# RX.net
KiCad netlist of a schematic drawn in EAGLE
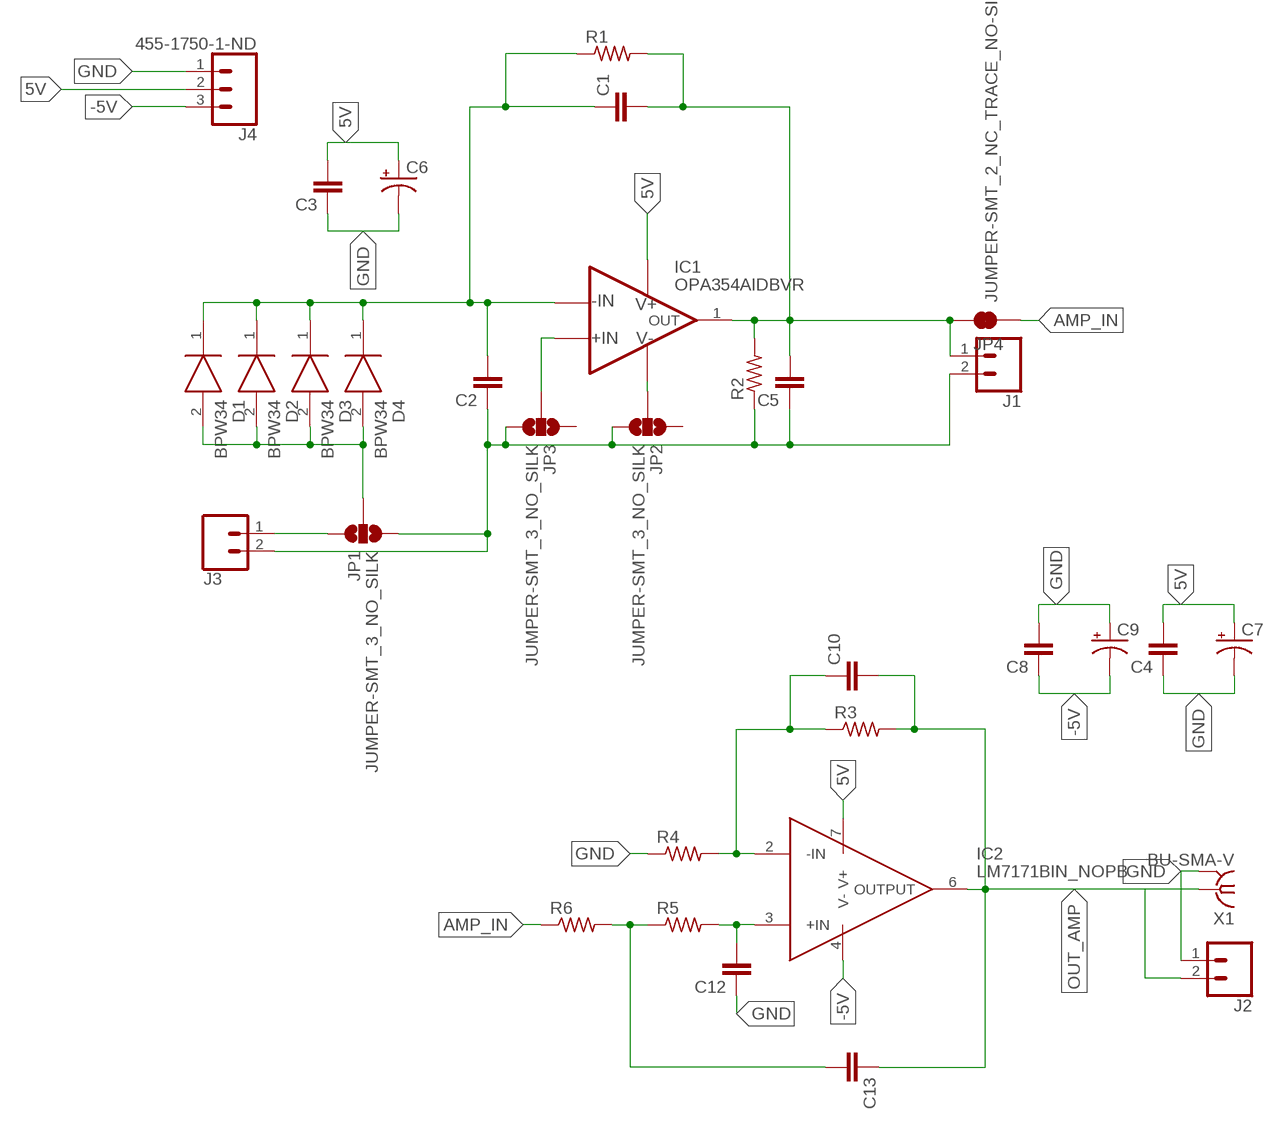
[diagram p0: schematic, sheet 1]
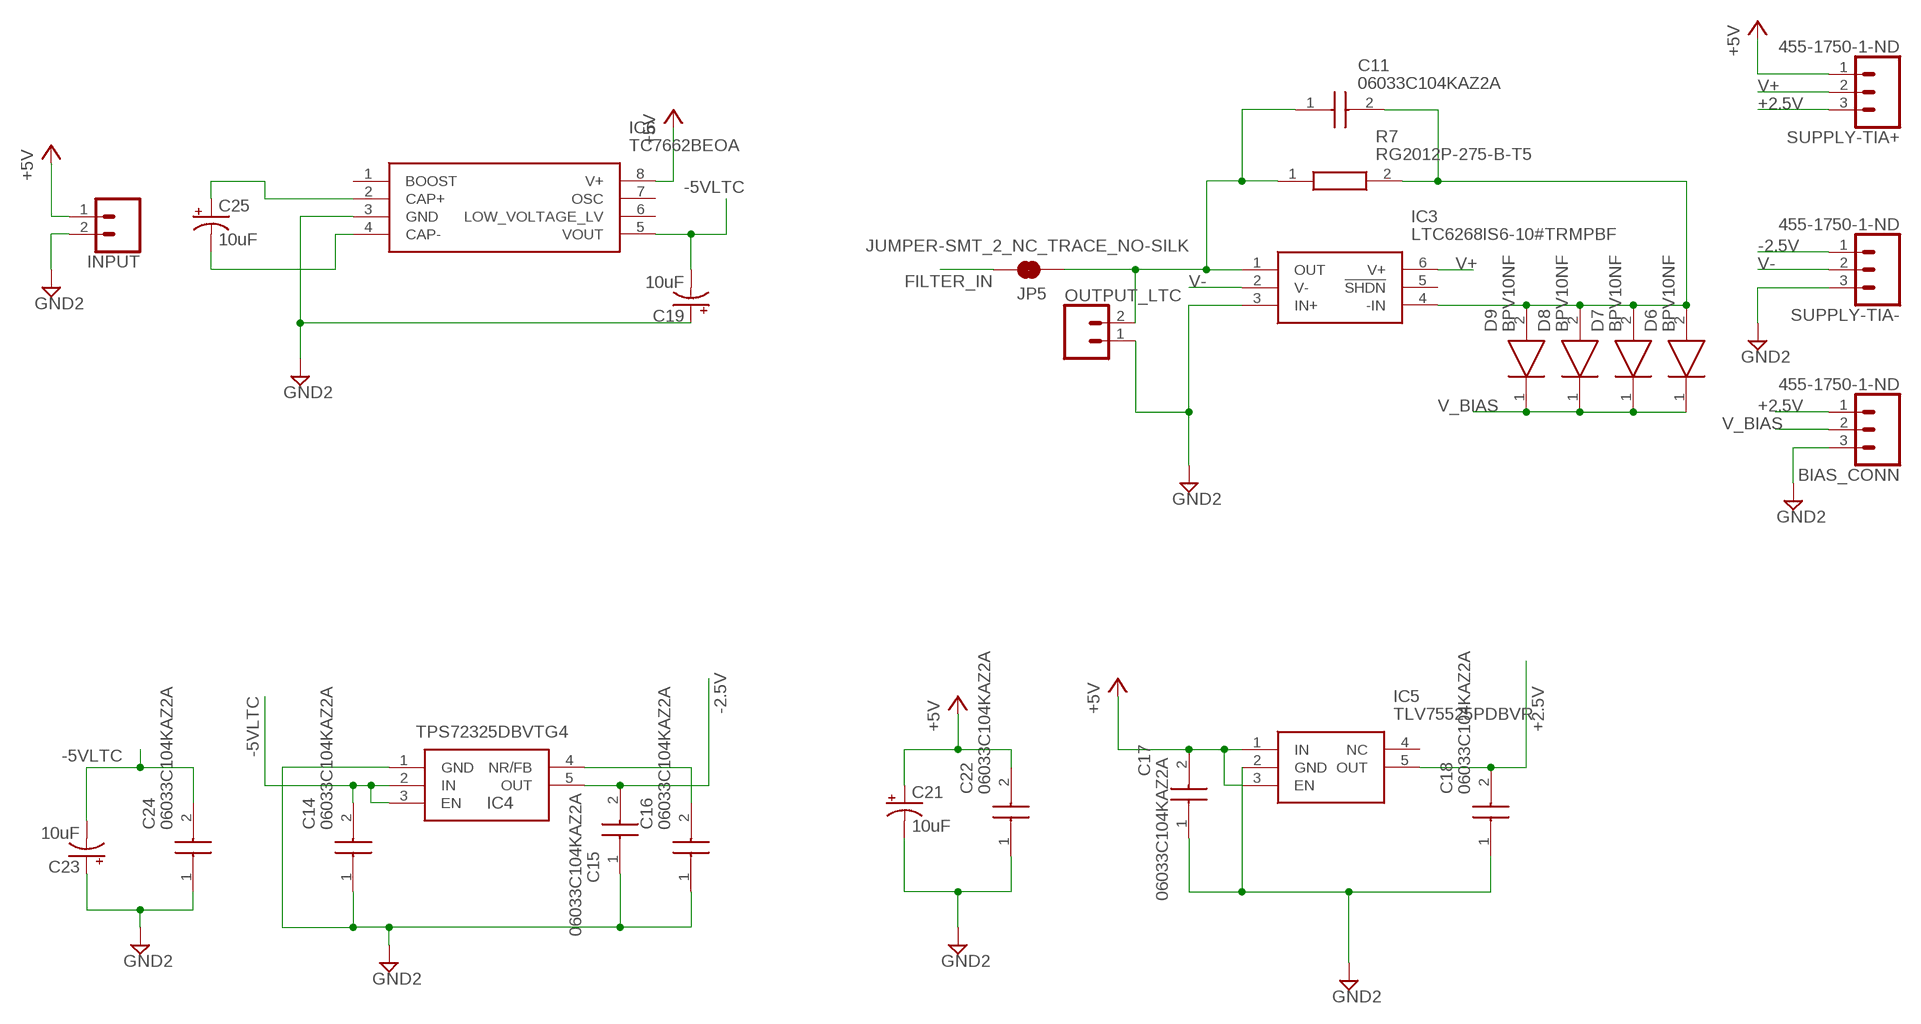
[diagram p1: schematic, sheet 2]
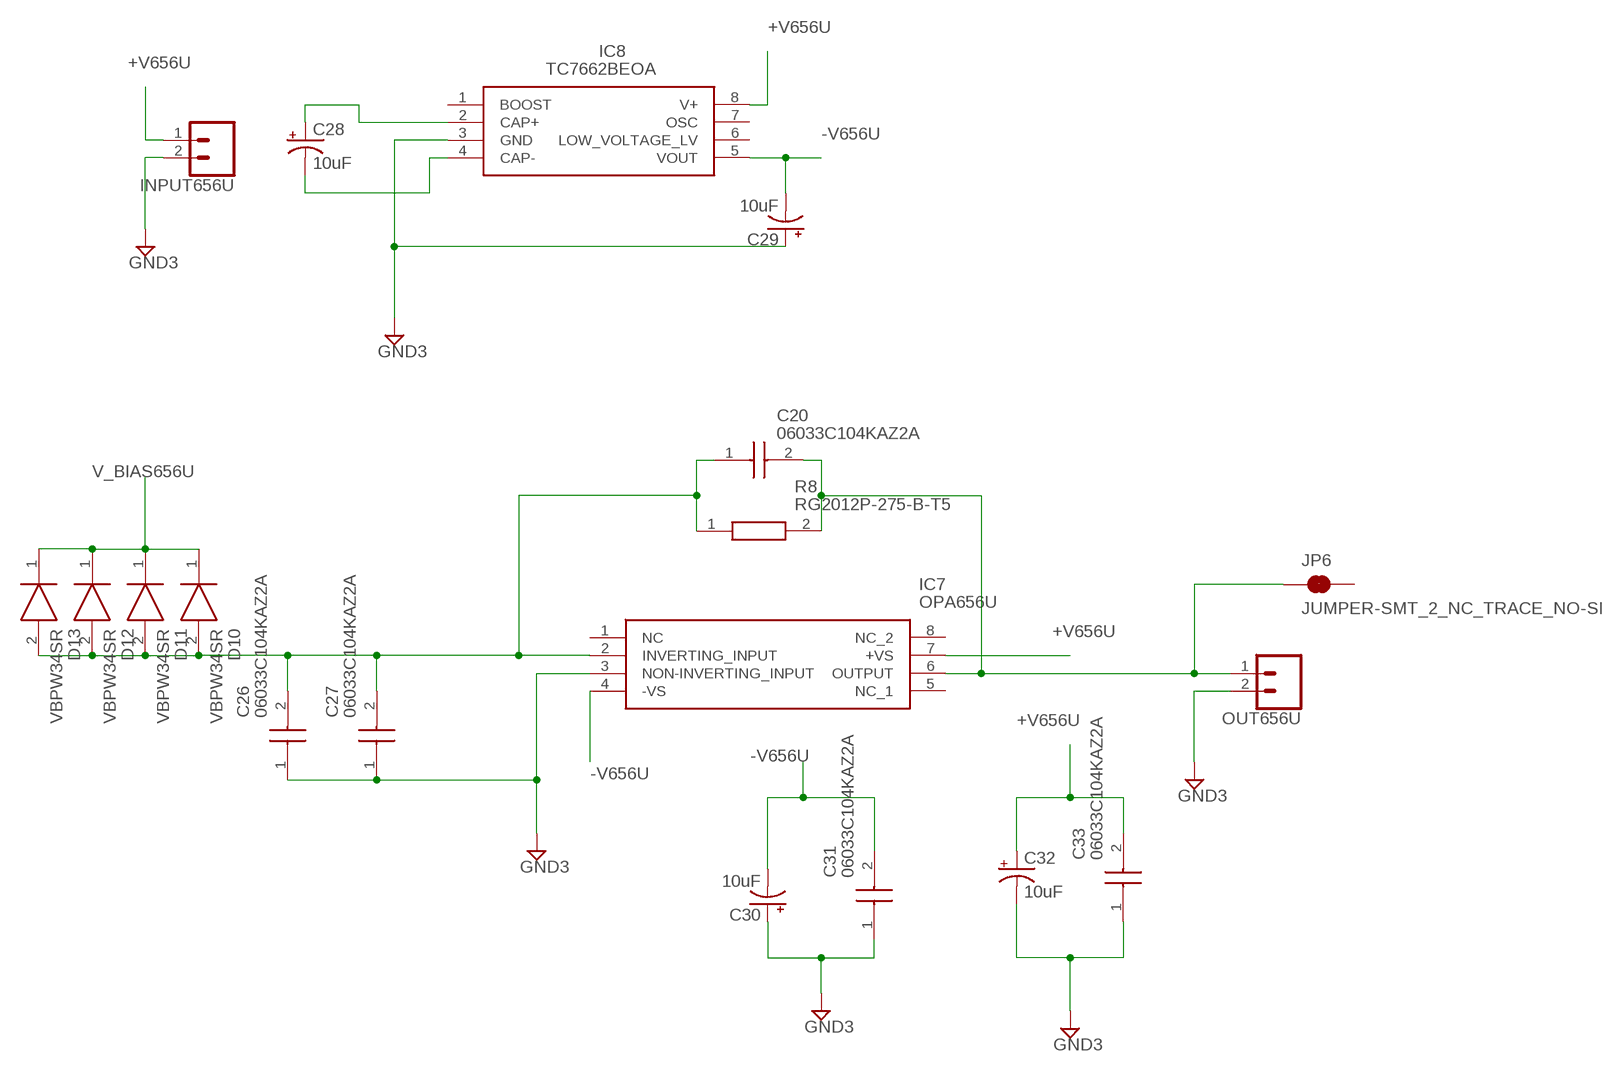
[diagram p2: schematic, sheet 3]

(export (version "E")
  (design (tool "Eeschema 10.0.6"))
  (components
    (comp (ref "BIAS_CONN")
      (value "455-1750-1-ND")
      (footprint "eagle-import:1X03")
      (libsource (lib "eagle-import") (part "CONN_03"))
    )
    (comp (ref "C11")
      (value "06033C104KAZ2A")
      (footprint "eagle-import:CAPC1608X90N")
      (fields
        (field (name "MOUSER_PART_NUMBER") "581-06033C104KAZ2A")
        (field (name "RS_PART_NUMBER") "1356596")
      )
      (libsource (lib "eagle-import") (part "06033C104KAZ2A"))
    )
    (comp (ref "C14")
      (value "06033C104KAZ2A")
      (footprint "eagle-import:CAPC1608X90N")
      (fields
        (field (name "MOUSER_PART_NUMBER") "581-06033C104KAZ2A")
        (field (name "RS_PART_NUMBER") "1356596")
      )
      (libsource (lib "eagle-import") (part "06033C104KAZ2A"))
    )
    (comp (ref "C15")
      (value "06033C104KAZ2A")
      (footprint "eagle-import:CAPC1608X90N")
      (fields
        (field (name "MOUSER_PART_NUMBER") "581-06033C104KAZ2A")
        (field (name "RS_PART_NUMBER") "1356596")
      )
      (libsource (lib "eagle-import") (part "06033C104KAZ2A"))
    )
    (comp (ref "C16")
      (value "06033C104KAZ2A")
      (footprint "eagle-import:CAPC1608X90N")
      (fields
        (field (name "MOUSER_PART_NUMBER") "581-06033C104KAZ2A")
        (field (name "RS_PART_NUMBER") "1356596")
      )
      (libsource (lib "eagle-import") (part "06033C104KAZ2A"))
    )
    (comp (ref "C17")
      (value "06033C104KAZ2A")
      (footprint "eagle-import:CAPC1608X90N")
      (fields
        (field (name "MOUSER_PART_NUMBER") "581-06033C104KAZ2A")
        (field (name "RS_PART_NUMBER") "1356596")
      )
      (libsource (lib "eagle-import") (part "06033C104KAZ2A"))
    )
    (comp (ref "C18")
      (value "06033C104KAZ2A")
      (footprint "eagle-import:CAPC1608X90N")
      (fields
        (field (name "MOUSER_PART_NUMBER") "581-06033C104KAZ2A")
        (field (name "RS_PART_NUMBER") "1356596")
      )
      (libsource (lib "eagle-import") (part "06033C104KAZ2A"))
    )
    (comp (ref "C19")
      (value "10uF")
      (footprint "eagle-import:0603-POLAR")
      (libsource (lib "eagle-import") (part "10UF-POLAR-0603-6.3V-20%(TANT)"))
    )
    (comp (ref "C21")
      (value "10uF")
      (footprint "eagle-import:0603-POLAR")
      (libsource (lib "eagle-import") (part "10UF-POLAR-0603-6.3V-20%(TANT)"))
    )
    (comp (ref "C22")
      (value "06033C104KAZ2A")
      (footprint "eagle-import:CAPC1608X90N")
      (fields
        (field (name "MOUSER_PART_NUMBER") "581-06033C104KAZ2A")
        (field (name "RS_PART_NUMBER") "1356596")
      )
      (libsource (lib "eagle-import") (part "06033C104KAZ2A"))
    )
    (comp (ref "C23")
      (value "10uF")
      (footprint "eagle-import:0603-POLAR")
      (libsource (lib "eagle-import") (part "10UF-POLAR-0603-6.3V-20%(TANT)"))
    )
    (comp (ref "C24")
      (value "06033C104KAZ2A")
      (footprint "eagle-import:CAPC1608X90N")
      (fields
        (field (name "MOUSER_PART_NUMBER") "581-06033C104KAZ2A")
        (field (name "RS_PART_NUMBER") "1356596")
      )
      (libsource (lib "eagle-import") (part "06033C104KAZ2A"))
    )
    (comp (ref "C25")
      (value "10uF")
      (footprint "eagle-import:0603-POLAR")
      (libsource (lib "eagle-import") (part "10UF-POLAR-0603-6.3V-20%(TANT)"))
    )
    (comp (ref "D6")
      (value "BPV10NF")
      (footprint "eagle-import:BPV10NF")
      (fields (field (name "MOUSER_PART_NUMBER") "782-BPV10NF") (field (name "RS_PART_NUMBER") "6997607P"))
      (libsource (lib "eagle-import") (part "BPV10NF"))
    )
    (comp (ref "D7")
      (value "BPV10NF")
      (footprint "eagle-import:BPV10NF")
      (fields (field (name "MOUSER_PART_NUMBER") "782-BPV10NF") (field (name "RS_PART_NUMBER") "6997607P"))
      (libsource (lib "eagle-import") (part "BPV10NF"))
    )
    (comp (ref "D8")
      (value "BPV10NF")
      (footprint "eagle-import:BPV10NF")
      (fields (field (name "MOUSER_PART_NUMBER") "782-BPV10NF") (field (name "RS_PART_NUMBER") "6997607P"))
      (libsource (lib "eagle-import") (part "BPV10NF"))
    )
    (comp (ref "D9")
      (value "BPV10NF")
      (footprint "eagle-import:BPV10NF")
      (fields (field (name "MOUSER_PART_NUMBER") "782-BPV10NF") (field (name "RS_PART_NUMBER") "6997607P"))
      (libsource (lib "eagle-import") (part "BPV10NF"))
    )
    (comp (ref "IC3")
      (value "LTC6268IS6-10#TRMPBF")
      (footprint "eagle-import:SOT95P280X90-6N")
      (fields (field (name "MOUSER_PART_NUMBER") "584-C6268IS6-10TMPF"))
      (libsource (lib "eagle-import") (part "LTC6268IS6-10#TRMPBF"))
    )
    (comp (ref "IC4")
      (value "TPS72325DBVTG4")
      (footprint "eagle-import:SOT95P280X145-5N")
      (fields (field (name "MOUSER_PART_NUMBER") "595-TPS72325DBVTG4"))
      (libsource (lib "eagle-import") (part "TPS72325DBVTG4"))
    )
    (comp (ref "IC5")
      (value "TLV75525PDBVR")
      (footprint "eagle-import:SOT95P280X145-5N")
      (fields (field (name "MOUSER_PART_NUMBER") "595-TLV75525PDBVR"))
      (libsource (lib "eagle-import") (part "TLV75525PDBVR"))
    )
    (comp (ref "IC6")
      (value "TC7662BEOA")
      (footprint "eagle-import:SOIC127P600X175-8N")
      (fields
        (field (name "MOUSER_PART_NUMBER") "579-TC7662BEOA")
        (field (name "RS_PART_NUMBER") "2509532389")
      )
      (libsource (lib "eagle-import") (part "TC7662BEOA"))
    )
    (comp (ref "INPUT")
      (value "CONN_02")
      (footprint "eagle-import:1X02")
      (libsource (lib "eagle-import") (part "CONN_02"))
    )
    (comp (ref "JP5")
      (value "JUMPER-SMT_2_NC_TRACE_NO-SILK")
      (footprint "eagle-import:SMT-JUMPER_2_NC_TRACE_NO-SILK")
      (libsource (lib "eagle-import") (part "JUMPER-SMT_2_NC_TRACE_NO-SILK"))
    )
    (comp (ref "OUTPUT_LTC")
      (value "CONN_02")
      (footprint "eagle-import:1X02")
      (libsource (lib "eagle-import") (part "CONN_02"))
    )
    (comp (ref "R7")
      (value "RG2012P-275-B-T5")
      (footprint "eagle-import:RESC2012X50N")
      (fields (field (name "MOUSER_PART_NUMBER") "754-RG2012P-275B-T5"))
      (libsource (lib "eagle-import") (part "RG2012P-275-B-T5"))
    )
    (comp (ref "SUPPLY-TIA+")
      (value "455-1750-1-ND")
      (footprint "eagle-import:1X03")
      (libsource (lib "eagle-import") (part "CONN_03"))
    )
    (comp (ref "SUPPLY-TIA-")
      (value "455-1750-1-ND")
      (footprint "eagle-import:1X03")
      (libsource (lib "eagle-import") (part "CONN_03"))
    )
    (comp (ref "C1")
      (value "C-EUC0603K")
      (footprint "eagle-import:C0603K")
      (libsource (lib "eagle-import") (part "C-EUC0603K"))
    )
    (comp (ref "C2")
      (value "C-EUC0603K")
      (footprint "eagle-import:C0603K")
      (libsource (lib "eagle-import") (part "C-EUC0603K"))
    )
    (comp (ref "C3")
      (value "C-EUC0603K")
      (footprint "eagle-import:C0603K")
      (libsource (lib "eagle-import") (part "C-EUC0603K"))
    )
    (comp (ref "C4")
      (value "C-EUC0603K")
      (footprint "eagle-import:C0603K")
      (libsource (lib "eagle-import") (part "C-EUC0603K"))
    )
    (comp (ref "C5")
      (value "C-EUC0603K")
      (footprint "eagle-import:C0603K")
      (libsource (lib "eagle-import") (part "C-EUC0603K"))
    )
    (comp (ref "C6")
      (value "CPOL-USR/2012-12R")
      (footprint "eagle-import:R_2012-12R")
      (libsource (lib "eagle-import") (part "CPOL-USR/2012-12R"))
    )
    (comp (ref "C7")
      (value "CPOL-USR/2012-12R")
      (footprint "eagle-import:R_2012-12R")
      (libsource (lib "eagle-import") (part "CPOL-USR/2012-12R"))
    )
    (comp (ref "C8")
      (value "C-EUC0603K")
      (footprint "eagle-import:C0603K")
      (libsource (lib "eagle-import") (part "C-EUC0603K"))
    )
    (comp (ref "C9")
      (value "CPOL-USR/2012-12R")
      (footprint "eagle-import:R_2012-12R")
      (libsource (lib "eagle-import") (part "CPOL-USR/2012-12R"))
    )
    (comp (ref "C10")
      (value "C-EUC0603K")
      (footprint "eagle-import:C0603K")
      (libsource (lib "eagle-import") (part "C-EUC0603K"))
    )
    (comp (ref "C12")
      (value "C-EUC0603K")
      (footprint "eagle-import:C0603K")
      (libsource (lib "eagle-import") (part "C-EUC0603K"))
    )
    (comp (ref "C13")
      (value "C-EUC0603K")
      (footprint "eagle-import:C0603K")
      (libsource (lib "eagle-import") (part "C-EUC0603K"))
    )
    (comp (ref "D1")
      (value "BPW34")
      (footprint "eagle-import:BPW34")
      (fields (field (name "MOUSER_PART_NUMBER") "782-BPW34") (field (name "RS_PART_NUMBER") "6997616P"))
      (libsource (lib "eagle-import") (part "BPW34"))
    )
    (comp (ref "D2")
      (value "BPW34")
      (footprint "eagle-import:BPW34")
      (fields (field (name "MOUSER_PART_NUMBER") "782-BPW34") (field (name "RS_PART_NUMBER") "6997616P"))
      (libsource (lib "eagle-import") (part "BPW34"))
    )
    (comp (ref "D3")
      (value "BPW34")
      (footprint "eagle-import:BPW34")
      (fields (field (name "MOUSER_PART_NUMBER") "782-BPW34") (field (name "RS_PART_NUMBER") "6997616P"))
      (libsource (lib "eagle-import") (part "BPW34"))
    )
    (comp (ref "D4")
      (value "BPW34")
      (footprint "eagle-import:BPW34")
      (fields (field (name "MOUSER_PART_NUMBER") "782-BPW34") (field (name "RS_PART_NUMBER") "6997616P"))
      (libsource (lib "eagle-import") (part "BPW34"))
    )
    (comp (ref "IC1")
      (value "OPA354AIDBVR")
      (footprint "eagle-import:SOT95P280X145-5N@1")
      (fields (field (name "MOUSER_PART_NUMBER") "595-OPA354AIDBVR"))
      (libsource (lib "eagle-import") (part "OPA354AIDBVR"))
    )
    (comp (ref "IC2")
      (value "LM7171BIN_NOPB")
      (footprint "eagle-import:DIP794W53P254L959H508Q8N")
      (fields
        (field (name "MANUFACTURER_PART_NUMBER") "LM7171BIN/NOPB")
        (field (name "MOUSER_PART_NUMBER") "926-LM7171BIN/NOPB")
        (field (name "RS_PART_NUMBER") "5343762P")
      )
      (libsource (lib "eagle-import") (part "LM7171BIN_NOPB"))
    )
    (comp (ref "J1")
      (value "CONN_02")
      (footprint "eagle-import:1X02")
      (libsource (lib "eagle-import") (part "CONN_02"))
    )
    (comp (ref "J2")
      (value "CONN_02")
      (footprint "eagle-import:1X02")
      (libsource (lib "eagle-import") (part "CONN_02"))
    )
    (comp (ref "J3")
      (value "CONN_02")
      (footprint "eagle-import:1X02")
      (libsource (lib "eagle-import") (part "CONN_02"))
    )
    (comp (ref "J4")
      (value "455-1750-1-ND")
      (footprint "eagle-import:1X03")
      (libsource (lib "eagle-import") (part "CONN_03"))
    )
    (comp (ref "JP1")
      (value "JUMPER-SMT_3_NO_SILK")
      (footprint "eagle-import:SMT-JUMPER_3_NO_SILK")
      (libsource (lib "eagle-import") (part "JUMPER-SMT_3_NO_SILK"))
    )
    (comp (ref "JP2")
      (value "JUMPER-SMT_3_NO_SILK")
      (footprint "eagle-import:SMT-JUMPER_3_NO_SILK")
      (libsource (lib "eagle-import") (part "JUMPER-SMT_3_NO_SILK"))
    )
    (comp (ref "JP3")
      (value "JUMPER-SMT_3_NO_SILK")
      (footprint "eagle-import:SMT-JUMPER_3_NO_SILK")
      (libsource (lib "eagle-import") (part "JUMPER-SMT_3_NO_SILK"))
    )
    (comp (ref "JP4")
      (value "JUMPER-SMT_2_NC_TRACE_NO-SILK")
      (footprint "eagle-import:SMT-JUMPER_2_NC_TRACE_NO-SILK")
      (libsource (lib "eagle-import") (part "JUMPER-SMT_2_NC_TRACE_NO-SILK"))
    )
    (comp (ref "R1")
      (value "R-US_R0805")
      (footprint "eagle-import:R0805")
      (libsource (lib "eagle-import") (part "rcl_334_R-US_R0805"))
    )
    (comp (ref "R2")
      (value "R-US_R0805")
      (footprint "eagle-import:R0805")
      (libsource (lib "eagle-import") (part "rcl_334_R-US_R0805"))
    )
    (comp (ref "R3")
      (value "R-US_R0805")
      (footprint "eagle-import:R0805")
      (libsource (lib "eagle-import") (part "R-US_R0805"))
    )
    (comp (ref "R4")
      (value "R-US_R0805")
      (footprint "eagle-import:R0805")
      (libsource (lib "eagle-import") (part "R-US_R0805"))
    )
    (comp (ref "R5")
      (value "R-US_R0805")
      (footprint "eagle-import:R0805")
      (libsource (lib "eagle-import") (part "R-US_R0805"))
    )
    (comp (ref "R6")
      (value "R-US_R0805")
      (footprint "eagle-import:R0805")
      (libsource (lib "eagle-import") (part "R-US_R0805"))
    )
    (comp (ref "X1")
      (value "BU-SMA-V")
      (footprint "eagle-import:BU-SMA-V")
      (libsource (lib "eagle-import") (part "BU-SMA-V"))
    )
    (comp (ref "C20")
      (value "06033C104KAZ2A")
      (footprint "eagle-import:CAPC1608X90N")
      (fields
        (field (name "MOUSER_PART_NUMBER") "581-06033C104KAZ2A")
        (field (name "RS_PART_NUMBER") "1356596")
      )
      (libsource (lib "eagle-import") (part "06033C104KAZ2A"))
    )
    (comp (ref "C26")
      (value "06033C104KAZ2A")
      (footprint "eagle-import:CAPC1608X90N")
      (fields
        (field (name "MOUSER_PART_NUMBER") "581-06033C104KAZ2A")
        (field (name "RS_PART_NUMBER") "1356596")
      )
      (libsource (lib "eagle-import") (part "06033C104KAZ2A"))
    )
    (comp (ref "C27")
      (value "06033C104KAZ2A")
      (footprint "eagle-import:CAPC1608X90N")
      (fields
        (field (name "MOUSER_PART_NUMBER") "581-06033C104KAZ2A")
        (field (name "RS_PART_NUMBER") "1356596")
      )
      (libsource (lib "eagle-import") (part "06033C104KAZ2A"))
    )
    (comp (ref "C28")
      (value "10uF")
      (footprint "eagle-import:0603-POLAR")
      (libsource (lib "eagle-import") (part "10UF-POLAR-0603-6.3V-20%(TANT)"))
    )
    (comp (ref "C29")
      (value "10uF")
      (footprint "eagle-import:0603-POLAR")
      (libsource (lib "eagle-import") (part "10UF-POLAR-0603-6.3V-20%(TANT)"))
    )
    (comp (ref "C30")
      (value "10uF")
      (footprint "eagle-import:0603-POLAR")
      (libsource (lib "eagle-import") (part "10UF-POLAR-0603-6.3V-20%(TANT)"))
    )
    (comp (ref "C31")
      (value "06033C104KAZ2A")
      (footprint "eagle-import:CAPC1608X90N")
      (fields
        (field (name "MOUSER_PART_NUMBER") "581-06033C104KAZ2A")
        (field (name "RS_PART_NUMBER") "1356596")
      )
      (libsource (lib "eagle-import") (part "06033C104KAZ2A"))
    )
    (comp (ref "C32")
      (value "10uF")
      (footprint "eagle-import:0603-POLAR")
      (libsource (lib "eagle-import") (part "10UF-POLAR-0603-6.3V-20%(TANT)"))
    )
    (comp (ref "C33")
      (value "06033C104KAZ2A")
      (footprint "eagle-import:CAPC1608X90N")
      (fields
        (field (name "MOUSER_PART_NUMBER") "581-06033C104KAZ2A")
        (field (name "RS_PART_NUMBER") "1356596")
      )
      (libsource (lib "eagle-import") (part "06033C104KAZ2A"))
    )
    (comp (ref "D10")
      (value "VBPW34SR")
      (footprint "eagle-import:VBPW34SR")
      (fields (field (name "MOUSER_PART_NUMBER") "782-VBPW34SR") (field (name "RS_PART_NUMBER") "9195813"))
      (libsource (lib "eagle-import") (part "VBPW34SR"))
    )
    (comp (ref "D11")
      (value "VBPW34SR")
      (footprint "eagle-import:VBPW34SR")
      (fields (field (name "MOUSER_PART_NUMBER") "782-VBPW34SR") (field (name "RS_PART_NUMBER") "9195813"))
      (libsource (lib "eagle-import") (part "VBPW34SR"))
    )
    (comp (ref "D12")
      (value "VBPW34SR")
      (footprint "eagle-import:VBPW34SR")
      (fields (field (name "MOUSER_PART_NUMBER") "782-VBPW34SR") (field (name "RS_PART_NUMBER") "9195813"))
      (libsource (lib "eagle-import") (part "VBPW34SR"))
    )
    (comp (ref "D13")
      (value "VBPW34SR")
      (footprint "eagle-import:VBPW34SR")
      (fields (field (name "MOUSER_PART_NUMBER") "782-VBPW34SR") (field (name "RS_PART_NUMBER") "9195813"))
      (libsource (lib "eagle-import") (part "VBPW34SR"))
    )
    (comp (ref "IC7")
      (value "OPA656U")
      (footprint "eagle-import:SOIC127P600X175-8N@1")
      (fields (field (name "MOUSER_PART_NUMBER") "595-OPA656U") (field (name "RS_PART_NUMBER") "6604368P"))
      (libsource (lib "eagle-import") (part "OPA656U"))
    )
    (comp (ref "IC8")
      (value "TC7662BEOA")
      (footprint "eagle-import:SOIC127P600X175-8N")
      (fields
        (field (name "MOUSER_PART_NUMBER") "579-TC7662BEOA")
        (field (name "RS_PART_NUMBER") "2509532389")
      )
      (libsource (lib "eagle-import") (part "TC7662BEOA"))
    )
    (comp (ref "INPUT656U")
      (value "CONN_02")
      (footprint "eagle-import:1X02")
      (libsource (lib "eagle-import") (part "CONN_02"))
    )
    (comp (ref "JP6")
      (value "JUMPER-SMT_2_NC_TRACE_NO-SILK")
      (footprint "eagle-import:SMT-JUMPER_2_NC_TRACE_NO-SILK")
      (libsource (lib "eagle-import") (part "JUMPER-SMT_2_NC_TRACE_NO-SILK"))
    )
    (comp (ref "OUT656U")
      (value "CONN_02")
      (footprint "eagle-import:1X02")
      (libsource (lib "eagle-import") (part "CONN_02"))
    )
    (comp (ref "R8")
      (value "RG2012P-275-B-T5")
      (footprint "eagle-import:RESC2012X50N")
      (fields (field (name "MOUSER_PART_NUMBER") "754-RG2012P-275B-T5"))
      (libsource (lib "eagle-import") (part "RG2012P-275-B-T5"))
    )
  )
  (nets
    (net (code "1") (name "+2.5V") (class "Default")
      (node (ref "BIAS_CONN") (pin "1") (pinfunction "1_1") (pintype "passive"))
      (node (ref "C18") (pin "2") (pinfunction "2_2") (pintype "bidirectional"))
      (node (ref "IC5") (pin "5") (pinfunction "OUT_5") (pintype "output"))
      (node (ref "SUPPLY-TIA+") (pin "3") (pinfunction "3_3") (pintype "passive"))
    )
    (net (code "2") (name "+5V") (class "Default")
      (node (ref "C17") (pin "2") (pinfunction "2_2") (pintype "bidirectional"))
      (node (ref "C21") (pin "+") (pinfunction "+_+") (pintype "passive"))
      (node (ref "C22") (pin "2") (pinfunction "2_2") (pintype "bidirectional"))
      (node (ref "IC5") (pin "1") (pinfunction "IN_1") (pintype "input"))
      (node (ref "IC5") (pin "3") (pinfunction "EN_3") (pintype "input"))
      (node (ref "IC6") (pin "8") (pinfunction "V+_8") (pintype "bidirectional"))
      (node (ref "INPUT") (pin "1") (pinfunction "1_1") (pintype "passive"))
      (node (ref "SUPPLY-TIA+") (pin "1") (pinfunction "1_1") (pintype "passive"))
    )
    (net (code "3") (name "+V656U") (class "Default")
      (node (ref "C32") (pin "+") (pinfunction "+_+") (pintype "passive"))
      (node (ref "C33") (pin "2") (pinfunction "2_2") (pintype "bidirectional"))
      (node (ref "IC7") (pin "7") (pinfunction "+VS_7") (pintype "bidirectional"))
      (node (ref "IC8") (pin "8") (pinfunction "V+_8") (pintype "bidirectional"))
      (node (ref "INPUT656U") (pin "1") (pinfunction "1_1") (pintype "passive"))
    )
    (net (code "4") (name "-2.5V") (class "Default")
      (node (ref "C15") (pin "2") (pinfunction "2_2") (pintype "bidirectional"))
      (node (ref "IC4") (pin "5") (pinfunction "OUT_5") (pintype "bidirectional"))
      (node (ref "SUPPLY-TIA-") (pin "1") (pinfunction "1_1") (pintype "passive"))
    )
    (net (code "5") (name "-5V") (class "Default")
      (node (ref "C8") (pin "1") (pinfunction "1_1") (pintype "passive"))
      (node (ref "C9") (pin "-") (pinfunction "-_-") (pintype "passive"))
      (node (ref "IC2") (pin "4") (pinfunction "V-_4") (pintype "power_in"))
      (node (ref "J4") (pin "3") (pinfunction "3_3") (pintype "passive"))
    )
    (net (code "6") (name "-5VLTC") (class "Default")
      (node (ref "C14") (pin "2") (pinfunction "2_2") (pintype "bidirectional"))
      (node (ref "C19") (pin "-") (pinfunction "-_-") (pintype "passive"))
      (node (ref "C23") (pin "-") (pinfunction "-_-") (pintype "passive"))
      (node (ref "C24") (pin "2") (pinfunction "2_2") (pintype "bidirectional"))
      (node (ref "IC4") (pin "2") (pinfunction "IN_2") (pintype "bidirectional"))
      (node (ref "IC4") (pin "3") (pinfunction "EN_3") (pintype "bidirectional"))
      (node (ref "IC6") (pin "5") (pinfunction "VOUT_5") (pintype "bidirectional"))
    )
    (net (code "7") (name "-V656U") (class "Default")
      (node (ref "C29") (pin "-") (pinfunction "-_-") (pintype "passive"))
      (node (ref "C30") (pin "-") (pinfunction "-_-") (pintype "passive"))
      (node (ref "C31") (pin "2") (pinfunction "2_2") (pintype "bidirectional"))
      (node (ref "IC7") (pin "4") (pinfunction "-VS_4") (pintype "bidirectional"))
      (node (ref "IC8") (pin "5") (pinfunction "VOUT_5") (pintype "bidirectional"))
    )
    (net (code "8") (name "5V") (class "Default")
      (node (ref "C3") (pin "2") (pinfunction "2_2") (pintype "passive"))
      (node (ref "C4") (pin "2") (pinfunction "2_2") (pintype "passive"))
      (node (ref "C6") (pin "+") (pinfunction "+_+") (pintype "passive"))
      (node (ref "C7") (pin "+") (pinfunction "+_+") (pintype "passive"))
      (node (ref "IC1") (pin "5") (pinfunction "V+_5") (pintype "power_in"))
      (node (ref "IC2") (pin "7") (pinfunction "V+_7") (pintype "power_in"))
      (node (ref "J4") (pin "2") (pinfunction "2_2") (pintype "passive"))
    )
    (net (code "9") (name "AMP_IN") (class "Default")
      (node (ref "JP4") (pin "1") (pinfunction "1_1") (pintype "passive"))
      (node (ref "R6") (pin "1") (pinfunction "1_1") (pintype "passive"))
    )
    (net (code "10") (name "FILTER_IN") (class "Default")
      (node (ref "JP5") (pin "2") (pinfunction "2_2") (pintype "passive"))
    )
    (net (code "11") (name "GND") (class "Default")
      (node (ref "C12") (pin "1") (pinfunction "1_1") (pintype "passive"))
      (node (ref "C2") (pin "1") (pinfunction "1_1") (pintype "passive"))
      (node (ref "C3") (pin "1") (pinfunction "1_1") (pintype "passive"))
      (node (ref "C4") (pin "1") (pinfunction "1_1") (pintype "passive"))
      (node (ref "C5") (pin "1") (pinfunction "1_1") (pintype "passive"))
      (node (ref "C6") (pin "-") (pinfunction "-_-") (pintype "passive"))
      (node (ref "C7") (pin "-") (pinfunction "-_-") (pintype "passive"))
      (node (ref "C8") (pin "2") (pinfunction "2_2") (pintype "passive"))
      (node (ref "C9") (pin "+") (pinfunction "+_+") (pintype "passive"))
      (node (ref "J1") (pin "2") (pinfunction "2_2") (pintype "passive"))
      (node (ref "J2") (pin "1") (pinfunction "1_1") (pintype "passive"))
      (node (ref "J3") (pin "2") (pinfunction "2_2") (pintype "passive"))
      (node (ref "J4") (pin "1") (pinfunction "1_1") (pintype "passive"))
      (node (ref "JP1") (pin "3") (pinfunction "3_3") (pintype "passive"))
      (node (ref "JP2") (pin "3") (pinfunction "3_3") (pintype "passive"))
      (node (ref "JP3") (pin "3") (pinfunction "3_3") (pintype "passive"))
      (node (ref "R2") (pin "1") (pinfunction "1_1") (pintype "passive"))
      (node (ref "R4") (pin "1") (pinfunction "1_1") (pintype "passive"))
      (node (ref "X1") (pin "2") (pinfunction "2_2") (pintype "passive"))
      (node (ref "X1") (pin "3") (pinfunction "2_3") (pintype "passive"))
      (node (ref "X1") (pin "4") (pinfunction "2_4") (pintype "passive"))
      (node (ref "X1") (pin "5") (pinfunction "2_5") (pintype "passive"))
    )
    (net (code "12") (name "GND2") (class "Default")
      (node (ref "BIAS_CONN") (pin "3") (pinfunction "3_3") (pintype "passive"))
      (node (ref "C14") (pin "1") (pinfunction "1_1") (pintype "bidirectional"))
      (node (ref "C15") (pin "1") (pinfunction "1_1") (pintype "bidirectional"))
      (node (ref "C16") (pin "1") (pinfunction "1_1") (pintype "bidirectional"))
      (node (ref "C17") (pin "1") (pinfunction "1_1") (pintype "bidirectional"))
      (node (ref "C18") (pin "1") (pinfunction "1_1") (pintype "bidirectional"))
      (node (ref "C19") (pin "+") (pinfunction "+_+") (pintype "passive"))
      (node (ref "C21") (pin "-") (pinfunction "-_-") (pintype "passive"))
      (node (ref "C22") (pin "1") (pinfunction "1_1") (pintype "bidirectional"))
      (node (ref "C23") (pin "+") (pinfunction "+_+") (pintype "passive"))
      (node (ref "C24") (pin "1") (pinfunction "1_1") (pintype "bidirectional"))
      (node (ref "IC3") (pin "3") (pinfunction "IN+_3") (pintype "bidirectional"))
      (node (ref "IC4") (pin "1") (pinfunction "GND_1") (pintype "bidirectional"))
      (node (ref "IC5") (pin "2") (pinfunction "GND_2") (pintype "power_in"))
      (node (ref "IC6") (pin "3") (pinfunction "GND_3") (pintype "bidirectional"))
      (node (ref "INPUT") (pin "2") (pinfunction "2_2") (pintype "passive"))
      (node (ref "OUTPUT_LTC") (pin "1") (pinfunction "1_1") (pintype "passive"))
      (node (ref "SUPPLY-TIA-") (pin "3") (pinfunction "3_3") (pintype "passive"))
    )
    (net (code "13") (name "GND3") (class "Default")
      (node (ref "C26") (pin "1") (pinfunction "1_1") (pintype "bidirectional"))
      (node (ref "C27") (pin "1") (pinfunction "1_1") (pintype "bidirectional"))
      (node (ref "C29") (pin "+") (pinfunction "+_+") (pintype "passive"))
      (node (ref "C30") (pin "+") (pinfunction "+_+") (pintype "passive"))
      (node (ref "C31") (pin "1") (pinfunction "1_1") (pintype "bidirectional"))
      (node (ref "C32") (pin "-") (pinfunction "-_-") (pintype "passive"))
      (node (ref "C33") (pin "1") (pinfunction "1_1") (pintype "bidirectional"))
      (node (ref "IC7") (pin "3") (pinfunction "NON-INVERTING_INPUT_3") (pintype "input"))
      (node (ref "IC8") (pin "3") (pinfunction "GND_3") (pintype "bidirectional"))
      (node (ref "INPUT656U") (pin "2") (pinfunction "2_2") (pintype "passive"))
      (node (ref "OUT656U") (pin "2") (pinfunction "2_2") (pintype "passive"))
    )
    (net (code "14") (name "Net-(C13-Pad2)") (class "Default")
      (node (ref "C13") (pin "2") (pinfunction "2_2") (pintype "passive"))
      (node (ref "R5") (pin "1") (pinfunction "1_1") (pintype "passive"))
      (node (ref "R6") (pin "2") (pinfunction "2_2") (pintype "passive"))
    )
    (net (code "15") (name "Net-(D1-A)") (class "Default")
      (node (ref "C1") (pin "1") (pinfunction "1_1") (pintype "passive"))
      (node (ref "C2") (pin "2") (pinfunction "2_2") (pintype "passive"))
      (node (ref "D1") (pin "1") (pinfunction "A_1") (pintype "bidirectional"))
      (node (ref "D2") (pin "1") (pinfunction "A_1") (pintype "bidirectional"))
      (node (ref "D3") (pin "1") (pinfunction "A_1") (pintype "bidirectional"))
      (node (ref "D4") (pin "1") (pinfunction "A_1") (pintype "bidirectional"))
      (node (ref "IC1") (pin "4") (pinfunction "-IN_4") (pintype "bidirectional"))
      (node (ref "R1") (pin "1") (pinfunction "1_1") (pintype "passive"))
    )
    (net (code "16") (name "Net-(D1-C)") (class "Default")
      (node (ref "D1") (pin "2") (pinfunction "C_2") (pintype "bidirectional"))
      (node (ref "D2") (pin "2") (pinfunction "C_2") (pintype "bidirectional"))
      (node (ref "D3") (pin "2") (pinfunction "C_2") (pintype "bidirectional"))
      (node (ref "D4") (pin "2") (pinfunction "C_2") (pintype "bidirectional"))
      (node (ref "JP1") (pin "2") (pinfunction "2_2") (pintype "passive"))
    )
    (net (code "17") (name "Net-(D6-A)") (class "Default")
      (node (ref "C11") (pin "2") (pinfunction "2_2") (pintype "bidirectional"))
      (node (ref "D6") (pin "2") (pinfunction "A_2") (pintype "bidirectional"))
      (node (ref "D7") (pin "2") (pinfunction "A_2") (pintype "bidirectional"))
      (node (ref "D8") (pin "2") (pinfunction "A_2") (pintype "bidirectional"))
      (node (ref "D9") (pin "2") (pinfunction "A_2") (pintype "bidirectional"))
      (node (ref "IC3") (pin "4") (pinfunction "-IN_4") (pintype "bidirectional"))
      (node (ref "R7") (pin "2") (pinfunction "2_2") (pintype "bidirectional"))
    )
    (net (code "18") (name "Net-(D10-A)") (class "Default")
      (node (ref "C20") (pin "1") (pinfunction "1_1") (pintype "bidirectional"))
      (node (ref "C26") (pin "2") (pinfunction "2_2") (pintype "bidirectional"))
      (node (ref "C27") (pin "2") (pinfunction "2_2") (pintype "bidirectional"))
      (node (ref "D10") (pin "2") (pinfunction "A_2") (pintype "bidirectional"))
      (node (ref "D11") (pin "2") (pinfunction "A_2") (pintype "bidirectional"))
      (node (ref "D12") (pin "2") (pinfunction "A_2") (pintype "bidirectional"))
      (node (ref "D13") (pin "2") (pinfunction "A_2") (pintype "bidirectional"))
      (node (ref "IC7") (pin "2") (pinfunction "INVERTING_INPUT_2") (pintype "input"))
      (node (ref "R8") (pin "1") (pinfunction "1_1") (pintype "bidirectional"))
    )
    (net (code "19") (name "Net-(IC1-+IN)") (class "Default")
      (node (ref "IC1") (pin "3") (pinfunction "+IN_3") (pintype "bidirectional"))
      (node (ref "JP3") (pin "2") (pinfunction "2_2") (pintype "passive"))
    )
    (net (code "20") (name "Net-(IC1-OUT)") (class "Default")
      (node (ref "C1") (pin "2") (pinfunction "2_2") (pintype "passive"))
      (node (ref "C5") (pin "2") (pinfunction "2_2") (pintype "passive"))
      (node (ref "IC1") (pin "1") (pinfunction "OUT_1") (pintype "bidirectional"))
      (node (ref "J1") (pin "1") (pinfunction "1_1") (pintype "passive"))
      (node (ref "JP4") (pin "2") (pinfunction "2_2") (pintype "passive"))
      (node (ref "R1") (pin "2") (pinfunction "2_2") (pintype "passive"))
      (node (ref "R2") (pin "2") (pinfunction "2_2") (pintype "passive"))
    )
    (net (code "21") (name "Net-(IC1-V-)") (class "Default")
      (node (ref "IC1") (pin "2") (pinfunction "V-_2") (pintype "power_in"))
      (node (ref "JP2") (pin "2") (pinfunction "2_2") (pintype "passive"))
    )
    (net (code "22") (name "Net-(IC2-+IN)") (class "Default")
      (node (ref "C12") (pin "2") (pinfunction "2_2") (pintype "passive"))
      (node (ref "IC2") (pin "3") (pinfunction "+IN_3") (pintype "input"))
      (node (ref "R5") (pin "2") (pinfunction "2_2") (pintype "passive"))
    )
    (net (code "23") (name "Net-(IC2--IN)") (class "Default")
      (node (ref "C10") (pin "1") (pinfunction "1_1") (pintype "passive"))
      (node (ref "IC2") (pin "2") (pinfunction "-IN_2") (pintype "input"))
      (node (ref "R3") (pin "1") (pinfunction "1_1") (pintype "passive"))
      (node (ref "R4") (pin "2") (pinfunction "2_2") (pintype "passive"))
    )
    (net (code "24") (name "Net-(IC3-OUT)") (class "Default")
      (node (ref "C11") (pin "1") (pinfunction "1_1") (pintype "bidirectional"))
      (node (ref "IC3") (pin "1") (pinfunction "OUT_1") (pintype "bidirectional"))
      (node (ref "JP5") (pin "1") (pinfunction "1_1") (pintype "passive"))
      (node (ref "OUTPUT_LTC") (pin "2") (pinfunction "2_2") (pintype "passive"))
      (node (ref "R7") (pin "1") (pinfunction "1_1") (pintype "bidirectional"))
    )
    (net (code "25") (name "Net-(IC4-NR{slash}FB)") (class "Default")
      (node (ref "C16") (pin "2") (pinfunction "2_2") (pintype "bidirectional"))
      (node (ref "IC4") (pin "4") (pinfunction "NR/FB_4") (pintype "bidirectional"))
    )
    (net (code "26") (name "Net-(IC6-CAP+)") (class "Default")
      (node (ref "C25") (pin "+") (pinfunction "+_+") (pintype "passive"))
      (node (ref "IC6") (pin "2") (pinfunction "CAP+_2") (pintype "bidirectional"))
    )
    (net (code "27") (name "Net-(IC6-CAP-)") (class "Default")
      (node (ref "C25") (pin "-") (pinfunction "-_-") (pintype "passive"))
      (node (ref "IC6") (pin "4") (pinfunction "CAP-_4") (pintype "bidirectional"))
    )
    (net (code "28") (name "Net-(IC7-OUTPUT)") (class "Default")
      (node (ref "C20") (pin "2") (pinfunction "2_2") (pintype "bidirectional"))
      (node (ref "IC7") (pin "6") (pinfunction "OUTPUT_6") (pintype "output"))
      (node (ref "JP6") (pin "1") (pinfunction "1_1") (pintype "passive"))
      (node (ref "OUT656U") (pin "1") (pinfunction "1_1") (pintype "passive"))
      (node (ref "R8") (pin "2") (pinfunction "2_2") (pintype "bidirectional"))
    )
    (net (code "29") (name "Net-(IC8-CAP+)") (class "Default")
      (node (ref "C28") (pin "+") (pinfunction "+_+") (pintype "passive"))
      (node (ref "IC8") (pin "2") (pinfunction "CAP+_2") (pintype "bidirectional"))
    )
    (net (code "30") (name "Net-(IC8-CAP-)") (class "Default")
      (node (ref "C28") (pin "-") (pinfunction "-_-") (pintype "passive"))
      (node (ref "IC8") (pin "4") (pinfunction "CAP-_4") (pintype "bidirectional"))
    )
    (net (code "31") (name "Net-(J3-Pad1)") (class "Default")
      (node (ref "J3") (pin "1") (pinfunction "1_1") (pintype "passive"))
      (node (ref "JP1") (pin "1") (pinfunction "1_1") (pintype "passive"))
    )
    (net (code "32") (name "OUT_AMP") (class "Default")
      (node (ref "C10") (pin "2") (pinfunction "2_2") (pintype "passive"))
      (node (ref "C13") (pin "1") (pinfunction "1_1") (pintype "passive"))
      (node (ref "IC2") (pin "6") (pinfunction "OUTPUT_6") (pintype "output"))
      (node (ref "J2") (pin "2") (pinfunction "2_2") (pintype "passive"))
      (node (ref "R3") (pin "2") (pinfunction "2_2") (pintype "passive"))
      (node (ref "X1") (pin "1") (pinfunction "1_1") (pintype "passive"))
    )
    (net (code "33") (name "V+") (class "Default")
      (node (ref "IC3") (pin "6") (pinfunction "V+_6") (pintype "bidirectional"))
      (node (ref "SUPPLY-TIA+") (pin "2") (pinfunction "2_2") (pintype "passive"))
    )
    (net (code "34") (name "V-") (class "Default")
      (node (ref "IC3") (pin "2") (pinfunction "V-_2") (pintype "bidirectional"))
      (node (ref "SUPPLY-TIA-") (pin "2") (pinfunction "2_2") (pintype "passive"))
    )
    (net (code "35") (name "V_BIAS") (class "Default")
      (node (ref "BIAS_CONN") (pin "2") (pinfunction "2_2") (pintype "passive"))
      (node (ref "D6") (pin "1") (pinfunction "K_1") (pintype "bidirectional"))
      (node (ref "D7") (pin "1") (pinfunction "K_1") (pintype "bidirectional"))
      (node (ref "D8") (pin "1") (pinfunction "K_1") (pintype "bidirectional"))
      (node (ref "D9") (pin "1") (pinfunction "K_1") (pintype "bidirectional"))
    )
    (net (code "36") (name "V_BIAS656U") (class "Default")
      (node (ref "D10") (pin "1") (pinfunction "K_1") (pintype "bidirectional"))
      (node (ref "D11") (pin "1") (pinfunction "K_1") (pintype "bidirectional"))
      (node (ref "D12") (pin "1") (pinfunction "K_1") (pintype "bidirectional"))
      (node (ref "D13") (pin "1") (pinfunction "K_1") (pintype "bidirectional"))
    )
    (net (code "37") (name "unconnected-(IC2-N{slash}C_1-Pad1)") (class "Default")
      (node (ref "IC2") (pin "1") (pinfunction "N/C_1_1") (pintype "bidirectional"))
    )
    (net (code "38") (name "unconnected-(IC2-N{slash}C_2-Pad5)") (class "Default")
      (node (ref "IC2") (pin "5") (pinfunction "N/C_2_5") (pintype "bidirectional"))
    )
    (net (code "39") (name "unconnected-(IC2-N{slash}C_3-Pad8)") (class "Default")
      (node (ref "IC2") (pin "8") (pinfunction "N/C_3_8") (pintype "bidirectional"))
    )
    (net (code "40") (name "unconnected-(IC3-~{SHDN}-Pad5)") (class "Default")
      (node (ref "IC3") (pin "5") (pinfunction "~{SHDN}_5") (pintype "bidirectional"))
    )
    (net (code "41") (name "unconnected-(IC5-NC-Pad4)") (class "Default")
      (node (ref "IC5") (pin "4") (pinfunction "NC_4") (pintype "no_connect"))
    )
    (net (code "42") (name "unconnected-(IC6-BOOST-Pad1)") (class "Default")
      (node (ref "IC6") (pin "1") (pinfunction "BOOST_1") (pintype "bidirectional"))
    )
    (net (code "43") (name "unconnected-(IC6-LOW_VOLTAGE_LV-Pad6)") (class "Default")
      (node (ref "IC6") (pin "6") (pinfunction "LOW_VOLTAGE_LV_6") (pintype "bidirectional"))
    )
    (net (code "44") (name "unconnected-(IC6-OSC-Pad7)") (class "Default")
      (node (ref "IC6") (pin "7") (pinfunction "OSC_7") (pintype "bidirectional"))
    )
    (net (code "45") (name "unconnected-(IC7-NC-Pad1)") (class "Default")
      (node (ref "IC7") (pin "1") (pinfunction "NC_1") (pintype "no_connect"))
    )
    (net (code "46") (name "unconnected-(IC7-NC_1-Pad5)") (class "Default")
      (node (ref "IC7") (pin "5") (pinfunction "NC_1_5") (pintype "bidirectional"))
    )
    (net (code "47") (name "unconnected-(IC7-NC_2-Pad8)") (class "Default")
      (node (ref "IC7") (pin "8") (pinfunction "NC_2_8") (pintype "bidirectional"))
    )
    (net (code "48") (name "unconnected-(IC8-BOOST-Pad1)") (class "Default")
      (node (ref "IC8") (pin "1") (pinfunction "BOOST_1") (pintype "bidirectional"))
    )
    (net (code "49") (name "unconnected-(IC8-LOW_VOLTAGE_LV-Pad6)") (class "Default")
      (node (ref "IC8") (pin "6") (pinfunction "LOW_VOLTAGE_LV_6") (pintype "bidirectional"))
    )
    (net (code "50") (name "unconnected-(IC8-OSC-Pad7)") (class "Default")
      (node (ref "IC8") (pin "7") (pinfunction "OSC_7") (pintype "bidirectional"))
    )
    (net (code "51") (name "unconnected-(JP2-Pad1)") (class "Default")
      (node (ref "JP2") (pin "1") (pinfunction "1_1") (pintype "passive"))
    )
    (net (code "52") (name "unconnected-(JP3-Pad1)") (class "Default")
      (node (ref "JP3") (pin "1") (pinfunction "1_1") (pintype "passive"))
    )
    (net (code "53") (name "unconnected-(JP6-Pad2)") (class "Default")
      (node (ref "JP6") (pin "2") (pinfunction "2_2") (pintype "passive"))
    )
  )
)
